# GMSL_SERIALIZER.net
KiCad netlist of a schematic drawn in Altium Designer
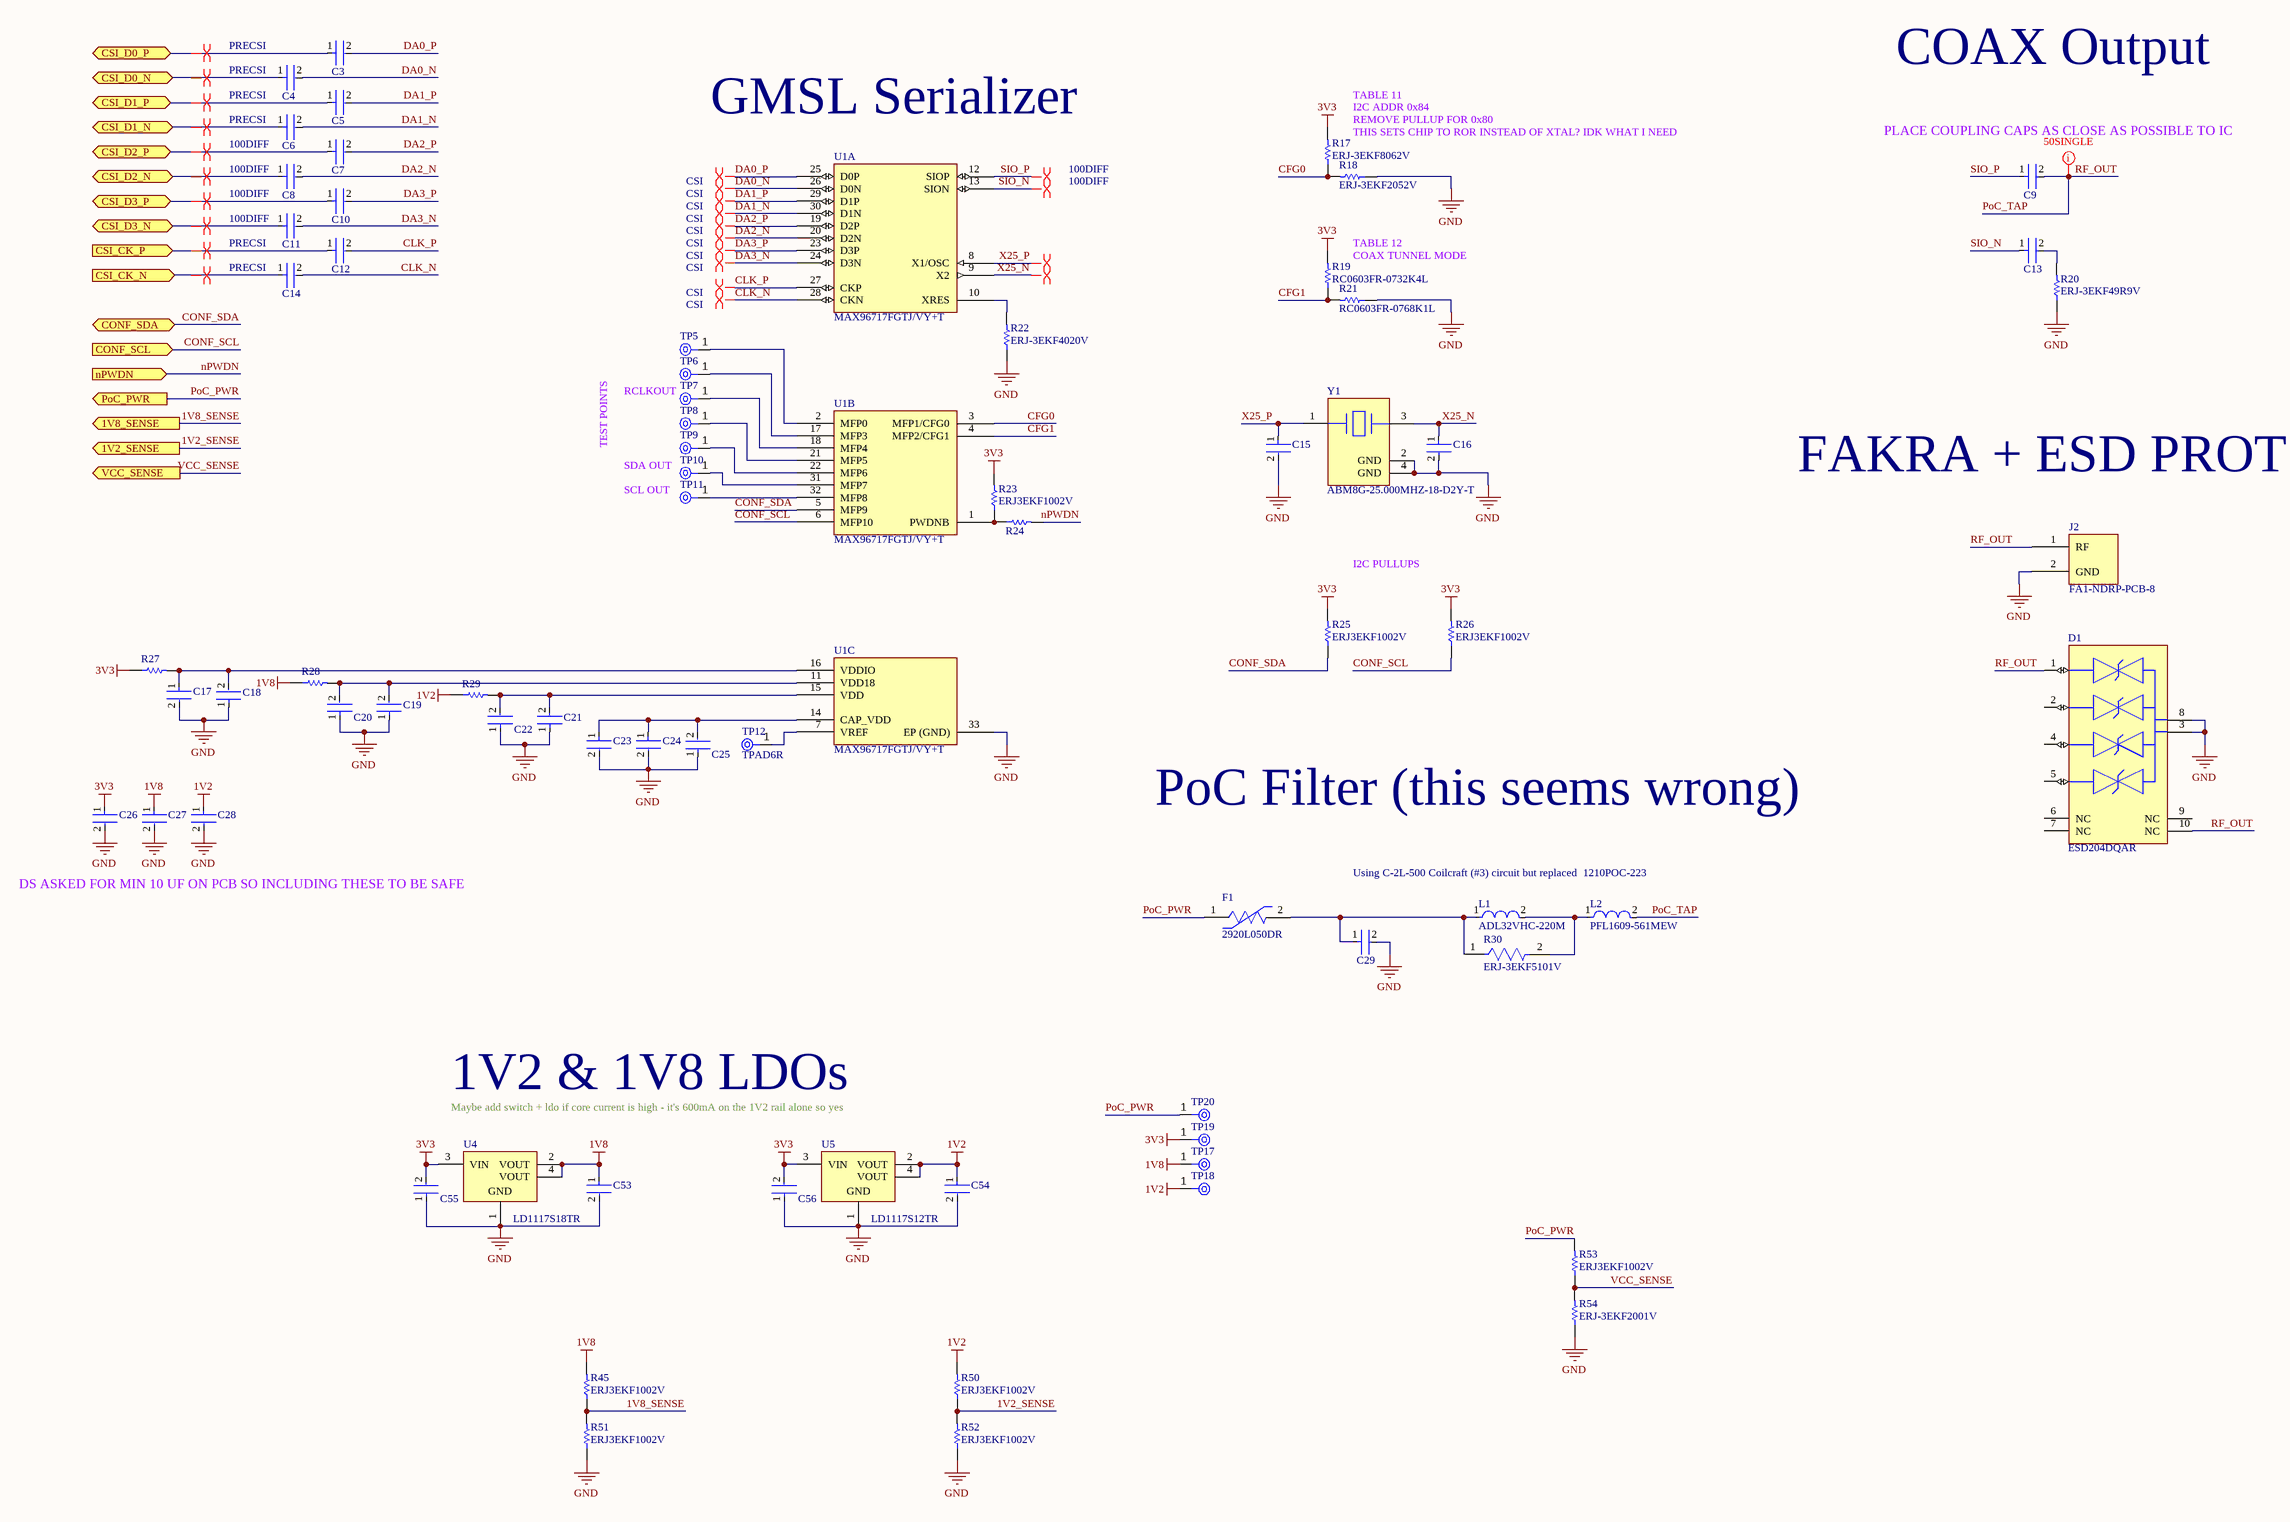
[diagram p0: GMSL_SERIALIZER.SchDoc]

(export (version "E")
  (design (tool "Eeschema 10.0.6"))
  (components
    (comp (ref "C3")
      (value "C1005X7R1H104K050BB")
      (footprint "FP-C1005-050-0_05-IPC_C")
      (description "Multilayer Ceramic Capacitors 100nF ±10% 50V X7R SMD 0402")
      (fields (field (name "VOLTAGE") "50V") (field (name "TOLERANCE") "10%"))
      (libsource (lib "Altium Content Vault") (part "b4654b650e69147ec39a6b967a45e02"))
    )
    (comp (ref "C4")
      (value "C1005X7R1H104K050BB")
      (footprint "FP-C1005-050-0_05-IPC_C")
      (description "Multilayer Ceramic Capacitors 100nF ±10% 50V X7R SMD 0402")
      (fields (field (name "VOLTAGE") "50V") (field (name "TOLERANCE") "10%"))
      (libsource (lib "Altium Content Vault") (part "b4654b650e69147ec39a6b967a45e02"))
    )
    (comp (ref "C5")
      (value "C1005X7R1H104K050BB")
      (footprint "FP-C1005-050-0_05-IPC_C")
      (description "Multilayer Ceramic Capacitors 100nF ±10% 50V X7R SMD 0402")
      (fields (field (name "VOLTAGE") "50V") (field (name "TOLERANCE") "10%"))
      (libsource (lib "Altium Content Vault") (part "b4654b650e69147ec39a6b967a45e02"))
    )
    (comp (ref "C6")
      (value "C1005X7R1H104K050BB")
      (footprint "FP-C1005-050-0_05-IPC_C")
      (description "Multilayer Ceramic Capacitors 100nF ±10% 50V X7R SMD 0402")
      (fields (field (name "VOLTAGE") "50V") (field (name "TOLERANCE") "10%"))
      (libsource (lib "Altium Content Vault") (part "b4654b650e69147ec39a6b967a45e02"))
    )
    (comp (ref "C7")
      (value "C1005X7R1H104K050BB")
      (footprint "FP-C1005-050-0_05-IPC_C")
      (description "Multilayer Ceramic Capacitors 100nF ±10% 50V X7R SMD 0402")
      (fields (field (name "VOLTAGE") "50V") (field (name "TOLERANCE") "10%"))
      (libsource (lib "Altium Content Vault") (part "b4654b650e69147ec39a6b967a45e02"))
    )
    (comp (ref "C8")
      (value "C1005X7R1H104K050BB")
      (footprint "FP-C1005-050-0_05-IPC_C")
      (description "Multilayer Ceramic Capacitors 100nF ±10% 50V X7R SMD 0402")
      (fields (field (name "VOLTAGE") "50V") (field (name "TOLERANCE") "10%"))
      (libsource (lib "Altium Content Vault") (part "b4654b650e69147ec39a6b967a45e02"))
    )
    (comp (ref "C9")
      (value "C1005X7R1H104K050BB")
      (footprint "FP-C1005-050-0_05-IPC_C")
      (description "Multilayer Ceramic Capacitors 100nF ±10% 50V X7R SMD 0402")
      (fields (field (name "VOLTAGE") "50V") (field (name "TOLERANCE") "10%"))
      (libsource (lib "Altium Content Vault") (part "b4654b650e69147ec39a6b967a45e02"))
    )
    (comp (ref "C10")
      (value "C1005X7R1H104K050BB")
      (footprint "FP-C1005-050-0_05-IPC_C")
      (description "Multilayer Ceramic Capacitors 100nF ±10% 50V X7R SMD 0402")
      (fields (field (name "VOLTAGE") "50V") (field (name "TOLERANCE") "10%"))
      (libsource (lib "Altium Content Vault") (part "b4654b650e69147ec39a6b967a45e02"))
    )
    (comp (ref "C11")
      (value "C1005X7R1H104K050BB")
      (footprint "FP-C1005-050-0_05-IPC_C")
      (description "Multilayer Ceramic Capacitors 100nF ±10% 50V X7R SMD 0402")
      (fields (field (name "VOLTAGE") "50V") (field (name "TOLERANCE") "10%"))
      (libsource (lib "Altium Content Vault") (part "b4654b650e69147ec39a6b967a45e02"))
    )
    (comp (ref "C12")
      (value "C1005X7R1H104K050BB")
      (footprint "FP-C1005-050-0_05-IPC_C")
      (description "Multilayer Ceramic Capacitors 100nF ±10% 50V X7R SMD 0402")
      (fields (field (name "VOLTAGE") "50V") (field (name "TOLERANCE") "10%"))
      (libsource (lib "Altium Content Vault") (part "b4654b650e69147ec39a6b967a45e02"))
    )
    (comp (ref "C13")
      (value "C1005X7R1H104K050BB")
      (footprint "FP-C1005-050-0_05-IPC_C")
      (description "Multilayer Ceramic Capacitors 100nF ±10% 50V X7R SMD 0402")
      (fields (field (name "VOLTAGE") "50V") (field (name "TOLERANCE") "10%"))
      (libsource (lib "Altium Content Vault") (part "b4654b650e69147ec39a6b967a45e02"))
    )
    (comp (ref "C14")
      (value "C1005X7R1H104K050BB")
      (footprint "FP-C1005-050-0_05-IPC_C")
      (description "Multilayer Ceramic Capacitors 100nF ±10% 50V X7R SMD 0402")
      (fields (field (name "VOLTAGE") "50V") (field (name "TOLERANCE") "10%"))
      (libsource (lib "Altium Content Vault") (part "b4654b650e69147ec39a6b967a45e02"))
    )
    (comp (ref "C15")
      (value "C0603C300J5GACTU")
      (footprint "FP-C0603C-CF-MFG")
      (description "CAP CER 30PF 50V 5% NP0 0603")
      (fields
        (field (name "MANUFACTURER") "KEMET")
        (field (name "OCTOPART") "https://octopart.com/c0603c300j5gactu-kemet-199455")
      )
      (libsource (lib "Altium Content Vault") (part "b4654b650e69147ec39a6b967a45e02"))
    )
    (comp (ref "C16")
      (value "C0603C300J5GACTU")
      (footprint "FP-C0603C-CF-MFG")
      (description "CAP CER 30PF 50V 5% NP0 0603")
      (fields
        (field (name "MANUFACTURER") "KEMET")
        (field (name "OCTOPART") "https://octopart.com/c0603c300j5gactu-kemet-199455")
      )
      (libsource (lib "Altium Content Vault") (part "b4654b650e69147ec39a6b967a45e02"))
    )
    (comp (ref "C17")
      (value "CL05A106MP5NUNC")
      (footprint "FP-CL05A106MP5NUNC-MFG")
      (description "CAP CER 10UF 10V X5R 0402")
      (fields
        (field (name "OCTOPART") "https://octopart.com/cl05a106mp5nunc-samsung-22457395")
        (field (name "TOLERANCE") "20%")
      )
      (libsource (lib "Altium Content Vault") (part "b4654b650e69147ec39a6b967a45e02"))
    )
    (comp (ref "C18")
      (value "C0402C103M5RACTU")
      (footprint "FP-C0402-BB-MFG")
      (description "CAP CER 10000PF 50V 20% X7R 0402")
      (fields
        (field (name "TOLERANCE") "0.2")
        (field (name "OCTOPART") "https://octopart.com/c0402c103m5ractu-kemet-17125571")
      )
      (libsource (lib "Altium Content Vault") (part "b4654b650e69147ec39a6b967a45e02"))
    )
    (comp (ref "C19")
      (value "C0402C103M5RACTU")
      (footprint "FP-C0402-BB-MFG")
      (description "CAP CER 10000PF 50V 20% X7R 0402")
      (fields
        (field (name "TOLERANCE") "0.2")
        (field (name "OCTOPART") "https://octopart.com/c0402c103m5ractu-kemet-17125571")
      )
      (libsource (lib "Altium Content Vault") (part "b4654b650e69147ec39a6b967a45e02"))
    )
    (comp (ref "C20")
      (value "C1005X7R1H104K050BB")
      (footprint "FP-C1005-050-0_05-IPC_C")
      (description "Multilayer Ceramic Capacitors 100nF ±10% 50V X7R SMD 0402")
      (fields (field (name "VOLTAGE") "50V") (field (name "TOLERANCE") "10%"))
      (libsource (lib "Altium Content Vault") (part "b4654b650e69147ec39a6b967a45e02"))
    )
    (comp (ref "C21")
      (value "C0402C103M5RACTU")
      (footprint "FP-C0402-BB-MFG")
      (description "CAP CER 10000PF 50V 20% X7R 0402")
      (fields
        (field (name "TOLERANCE") "0.2")
        (field (name "OCTOPART") "https://octopart.com/c0402c103m5ractu-kemet-17125571")
      )
      (libsource (lib "Altium Content Vault") (part "b4654b650e69147ec39a6b967a45e02"))
    )
    (comp (ref "C22")
      (value "C1005X7R1H104K050BB")
      (footprint "FP-C1005-050-0_05-IPC_C")
      (description "Multilayer Ceramic Capacitors 100nF ±10% 50V X7R SMD 0402")
      (fields (field (name "VOLTAGE") "50V") (field (name "TOLERANCE") "10%"))
      (libsource (lib "Altium Content Vault") (part "b4654b650e69147ec39a6b967a45e02"))
    )
    (comp (ref "C23")
      (value "CL05A106MP5NUNC")
      (footprint "FP-CL05A106MP5NUNC-MFG")
      (description "CAP CER 10UF 10V X5R 0402")
      (fields
        (field (name "OCTOPART") "https://octopart.com/cl05a106mp5nunc-samsung-22457395")
        (field (name "TOLERANCE") "20%")
      )
      (libsource (lib "Altium Content Vault") (part "b4654b650e69147ec39a6b967a45e02"))
    )
    (comp (ref "C24")
      (value "CL05A106MP5NUNC")
      (footprint "FP-CL05A106MP5NUNC-MFG")
      (description "CAP CER 10UF 10V X5R 0402")
      (fields
        (field (name "OCTOPART") "https://octopart.com/cl05a106mp5nunc-samsung-22457395")
        (field (name "TOLERANCE") "20%")
      )
      (libsource (lib "Altium Content Vault") (part "b4654b650e69147ec39a6b967a45e02"))
    )
    (comp (ref "C25")
      (value "C1005X7R1H104K050BB")
      (footprint "FP-C1005-050-0_05-IPC_C")
      (description "Multilayer Ceramic Capacitors 100nF ±10% 50V X7R SMD 0402")
      (fields (field (name "VOLTAGE") "50V") (field (name "TOLERANCE") "10%"))
      (libsource (lib "Altium Content Vault") (part "b4654b650e69147ec39a6b967a45e02"))
    )
    (comp (ref "C26")
      (value "CL05A106MP5NUNC")
      (footprint "FP-CL05A106MP5NUNC-MFG")
      (description "CAP CER 10UF 10V X5R 0402")
      (fields
        (field (name "OCTOPART") "https://octopart.com/cl05a106mp5nunc-samsung-22457395")
        (field (name "TOLERANCE") "20%")
      )
      (libsource (lib "Altium Content Vault") (part "b4654b650e69147ec39a6b967a45e02"))
    )
    (comp (ref "C27")
      (value "CL05A106MP5NUNC")
      (footprint "FP-CL05A106MP5NUNC-MFG")
      (description "CAP CER 10UF 10V X5R 0402")
      (fields
        (field (name "OCTOPART") "https://octopart.com/cl05a106mp5nunc-samsung-22457395")
        (field (name "TOLERANCE") "20%")
      )
      (libsource (lib "Altium Content Vault") (part "b4654b650e69147ec39a6b967a45e02"))
    )
    (comp (ref "C28")
      (value "CL05A106MP5NUNC")
      (footprint "FP-CL05A106MP5NUNC-MFG")
      (description "CAP CER 10UF 10V X5R 0402")
      (fields
        (field (name "OCTOPART") "https://octopart.com/cl05a106mp5nunc-samsung-22457395")
        (field (name "TOLERANCE") "20%")
      )
      (libsource (lib "Altium Content Vault") (part "b4654b650e69147ec39a6b967a45e02"))
    )
    (comp (ref "C29")
      (value "GRM21BR61E226ME44L")
      (footprint "FP-GRM21B-0_2-e0_2_0_7-IPC_B")
      (description "Chip Multilayer Ceramic Capacitors for General Purpose, 0805, 22uF, X5R, 15%, 20%, 25V")
      (fields (field (name "TOLERANCE") "20%") (field (name "VOLTAGE") "25V"))
      (libsource (lib "Altium Content Vault") (part "b4654b650e69147ec39a6b967a45e02"))
    )
    (comp (ref "C53")
      (value "GRM188R60J106ME47D")
      (footprint "FP-GRM188-0_1-e0_2_0_55-IPC_A")
      (description "Chip Multilayer Ceramic Capacitors for General Purpose, 0603, 10uF, X5R, 15%, 20%, 6.3V")
      (fields (field (name "VOLTAGE") "6.3V") (field (name "TOLERANCE") "20%"))
      (libsource (lib "Altium Content Vault") (part "02cd4be3c70576c341d710602a673aa"))
    )
    (comp (ref "C54")
      (value "GRM188R60J106ME47D")
      (footprint "FP-GRM188-0_1-e0_2_0_55-IPC_A")
      (description "Chip Multilayer Ceramic Capacitors for General Purpose, 0603, 10uF, X5R, 15%, 20%, 6.3V")
      (fields (field (name "VOLTAGE") "6.3V") (field (name "TOLERANCE") "20%"))
      (libsource (lib "Altium Content Vault") (part "02cd4be3c70576c341d710602a673aa"))
    )
    (comp (ref "C55")
      (value "C1005X7R1H104K050BB")
      (footprint "FP-C1005-050-0_05-IPC_C")
      (description "Multilayer Ceramic Capacitors 100nF ±10% 50V X7R SMD 0402")
      (fields (field (name "VOLTAGE") "50V") (field (name "TOLERANCE") "10%"))
      (libsource (lib "Altium Content Vault") (part "b4654b650e69147ec39a6b967a45e02"))
    )
    (comp (ref "C56")
      (value "C1005X7R1H104K050BB")
      (footprint "FP-C1005-050-0_05-IPC_C")
      (description "Multilayer Ceramic Capacitors 100nF ±10% 50V X7R SMD 0402")
      (fields (field (name "VOLTAGE") "50V") (field (name "TOLERANCE") "10%"))
      (libsource (lib "Altium Content Vault") (part "b4654b650e69147ec39a6b967a45e02"))
    )
    (comp (ref "D1")
      (value "ESD204DQAR")
      (footprint "FP-DQA0010A-MFG")
      (description "4-CHANNEL LOW-CAPACITANCE SURGE")
      (fields
        (field (name "MANUFACTURER") "Texas Instruments")
        (field (name "OCTOPART") "https://octopart.com/esd204dqar-texas+instruments-89917476")
      )
      (libsource (lib "Altium Content Vault") (part "1465e58c1818c7767b55926832f0bf5"))
    )
    (comp (ref "F1")
      (value "2920L050DR")
      (footprint "FP-2920L050DR-MFG")
      (description "PTC RESET FUSE 60V 500MA 2920")
      (libsource (lib "Altium Content Vault") (part "1c6d77a0208143737455a0c7eb396be"))
    )
    (comp (ref "J2")
      (value "FA1-NDRP-PCB-8")
      (footprint "FA1-NDRP-PCB-8-Footprint-1")
      (description "RF F Connector, Male, Board Mount, Solder Terminal, Plug")
      (libsource (lib "Space Concordia") (part "FA1-NDRP-PCB-8"))
    )
    (comp (ref "L1")
      (value "ADL32VHC-220M")
      (footprint "FP-1210POC-MFG")
      (description "NOT COILCRAFT - ACTUAL P# --> ADL32VHC-220M\r\n - Power Injection Chokes for PoC")
      (fields
        (field (name "MANUFACTURER") "coilcraft")
        (field (name "OCTOPART") "https://octopart.com/1210poc-223mrc-coilcraft-103207315")
      )
      (libsource (lib "Altium Content Vault") (part "725321dda6339637d4d059423bc1c3c"))
    )
    (comp (ref "L2")
      (value "PFL1609-561MEW")
      (footprint "FP-PFL1609-MFG")
      (description "Fixed Inductors PFL1609 Low Profile 0.56 uH 20 % 1.4 A")
      (fields (field (name "MANUFACTURER") "coilcraft") (field (name "TOLERANCE") "20%"))
      (libsource (lib "Altium Content Vault") (part "725321dda6339637d4d059423bc1c3c"))
    )
    (comp (ref "R17")
      (value "ERJ-3EKF8062V")
      (footprint "RESC1608X55X30LL15T15")
      (fields (field (name "MANUFACTURER") "Panasonic"))
      (libsource (lib "Altium Content Vault") (part "RES"))
    )
    (comp (ref "R18")
      (value "ERJ-3EKF2052V")
      (footprint "RESC1608X55X30NL15T15")
      (fields (field (name "MANUFACTURER") "Panasonic"))
      (libsource (lib "Altium Content Vault") (part "RES"))
    )
    (comp (ref "R19")
      (value "RC0603FR-0732K4L")
      (footprint "RESC1608X55X25ML10T15")
      (fields (field (name "MANUFACTURER") "Yageo"))
      (libsource (lib "Altium Content Vault") (part "RES"))
    )
    (comp (ref "R20")
      (value "ERJ-3EKF49R9V")
      (footprint "RESC1608X55X30ML15T15")
      (fields (field (name "MANUFACTURER") "Panasonic"))
      (libsource (lib "Altium Content Vault") (part "RES"))
    )
    (comp (ref "R21")
      (value "RC0603FR-0768K1L")
      (footprint "RESC1608X55X25LL10T15")
      (fields (field (name "MANUFACTURER") "Yageo"))
      (libsource (lib "Altium Content Vault") (part "RES"))
    )
    (comp (ref "R22")
      (value "ERJ-3EKF4020V")
      (footprint "RESC1608X55X30LL15T15")
      (fields (field (name "MANUFACTURER") "Panasonic"))
      (libsource (lib "Altium Content Vault") (part "RES"))
    )
    (comp (ref "R23")
      (value "ERJ3EKF1002V")
      (footprint "RESC1609X55X30LL15T15")
      (description "Chip Resistor, 10 KOhm, +/- 1%, 0.1 W, -55 to 155 degC, 0603 (1608 Metric), RoHS, Tape and Reel")
      (fields (field (name "TOLERANCE") "1%") (field (name "MANUFACTURER") "Panasonic"))
      (libsource (lib "Altium Content Vault") (part "RES-2"))
    )
    (comp (ref "R24")
      (value "0402 JUMPER")
      (footprint "RESC1005X40X25ML05T05")
      (description "READ THE NAME")
      (libsource (lib "Space Concordia") (part "CMP-009-00206-2"))
    )
    (comp (ref "R25")
      (value "ERJ3EKF1002V")
      (footprint "RESC1609X55X30LL15T15")
      (description "Chip Resistor, 10 KOhm, +/- 1%, 0.1 W, -55 to 155 degC, 0603 (1608 Metric), RoHS, Tape and Reel")
      (fields (field (name "TOLERANCE") "1%") (field (name "MANUFACTURER") "Panasonic"))
      (libsource (lib "Altium Content Vault") (part "RES-2"))
    )
    (comp (ref "R26")
      (value "ERJ3EKF1002V")
      (footprint "RESC1609X55X30LL15T15")
      (description "Chip Resistor, 10 KOhm, +/- 1%, 0.1 W, -55 to 155 degC, 0603 (1608 Metric), RoHS, Tape and Reel")
      (fields (field (name "TOLERANCE") "1%") (field (name "MANUFACTURER") "Panasonic"))
      (libsource (lib "Altium Content Vault") (part "RES-2"))
    )
    (comp (ref "R27")
      (value "RC0402JR-070RL")
      (footprint "RESC1005X40X25NL05T10")
      (fields (field (name "MANUFACTURER") "Yageo / Phycomp"))
      (libsource (lib "Altium Content Vault") (part "RES"))
    )
    (comp (ref "R28")
      (value "RC0402JR-070RL")
      (footprint "RESC1005X40X25NL05T10")
      (fields (field (name "MANUFACTURER") "Yageo / Phycomp"))
      (libsource (lib "Altium Content Vault") (part "RES"))
    )
    (comp (ref "R29")
      (value "RC0402JR-070RL")
      (footprint "RESC1005X40X25NL05T10")
      (fields (field (name "MANUFACTURER") "Yageo / Phycomp"))
      (libsource (lib "Altium Content Vault") (part "RES"))
    )
    (comp (ref "R30")
      (value "ERJ-3EKF5101V")
      (footprint "FP-ERJ3EK-MFG")
      (description "RES SMD 5.1K OHM 1% 1/10W 0603")
      (fields (field (name "TOLERANCE") "1%"))
      (libsource (lib "Altium Content Vault") (part "1029c3af85768c4190bb7ad29bc67b5"))
    )
    (comp (ref "R45")
      (value "ERJ3EKF1002V")
      (footprint "RESC1609X55X30LL15T15")
      (description "Chip Resistor, 10 KOhm, +/- 1%, 0.1 W, -55 to 155 degC, 0603 (1608 Metric), RoHS, Tape and Reel")
      (fields (field (name "TOLERANCE") "1%") (field (name "MANUFACTURER") "Panasonic"))
      (libsource (lib "Altium Content Vault") (part "RES-2"))
    )
    (comp (ref "R50")
      (value "ERJ3EKF1002V")
      (footprint "RESC1609X55X30LL15T15")
      (description "Chip Resistor, 10 KOhm, +/- 1%, 0.1 W, -55 to 155 degC, 0603 (1608 Metric), RoHS, Tape and Reel")
      (fields (field (name "TOLERANCE") "1%") (field (name "MANUFACTURER") "Panasonic"))
      (libsource (lib "Altium Content Vault") (part "RES-2"))
    )
    (comp (ref "R51")
      (value "ERJ3EKF1002V")
      (footprint "RESC1609X55X30LL15T15")
      (description "Chip Resistor, 10 KOhm, +/- 1%, 0.1 W, -55 to 155 degC, 0603 (1608 Metric), RoHS, Tape and Reel")
      (fields (field (name "TOLERANCE") "1%") (field (name "MANUFACTURER") "Panasonic"))
      (libsource (lib "Altium Content Vault") (part "RES-2"))
    )
    (comp (ref "R52")
      (value "ERJ3EKF1002V")
      (footprint "RESC1609X55X30LL15T15")
      (description "Chip Resistor, 10 KOhm, +/- 1%, 0.1 W, -55 to 155 degC, 0603 (1608 Metric), RoHS, Tape and Reel")
      (fields (field (name "TOLERANCE") "1%") (field (name "MANUFACTURER") "Panasonic"))
      (libsource (lib "Altium Content Vault") (part "RES-2"))
    )
    (comp (ref "R53")
      (value "ERJ3EKF1002V")
      (footprint "RESC1609X55X30LL15T15")
      (description "Chip Resistor, 10 KOhm, +/- 1%, 0.1 W, -55 to 155 degC, 0603 (1608 Metric), RoHS, Tape and Reel")
      (fields (field (name "TOLERANCE") "1%") (field (name "MANUFACTURER") "Panasonic"))
      (libsource (lib "Altium Content Vault") (part "RES-2"))
    )
    (comp (ref "R54")
      (value "ERJ-3EKF2001V")
      (footprint "RESC1608X55X30ML15T15")
      (fields (field (name "MANUFACTURER") "Panasonic"))
      (libsource (lib "Altium Content Vault") (part "RES"))
    )
    (comp (ref "TP5")
      (value "TPAD6R")
      (footprint "New footprint 1")
      (description "Test Point .6mm")
      (libsource (lib "Space Concordia") (part "TP"))
    )
    (comp (ref "TP6")
      (value "TPAD6R")
      (footprint "New footprint 1")
      (description "Test Point .6mm")
      (libsource (lib "Space Concordia") (part "TP"))
    )
    (comp (ref "TP7")
      (value "TPAD6R")
      (footprint "New footprint 1")
      (description "Test Point .6mm")
      (libsource (lib "Space Concordia") (part "TP"))
    )
    (comp (ref "TP8")
      (value "TPAD6R")
      (footprint "New footprint 1")
      (description "Test Point .6mm")
      (libsource (lib "Space Concordia") (part "TP"))
    )
    (comp (ref "TP9")
      (value "TPAD6R")
      (footprint "New footprint 1")
      (description "Test Point .6mm")
      (libsource (lib "Space Concordia") (part "TP"))
    )
    (comp (ref "TP10")
      (value "TPAD6R")
      (footprint "New footprint 1")
      (description "Test Point .6mm")
      (libsource (lib "Space Concordia") (part "TP"))
    )
    (comp (ref "TP11")
      (value "TPAD6R")
      (footprint "New footprint 1")
      (description "Test Point .6mm")
      (libsource (lib "Space Concordia") (part "TP"))
    )
    (comp (ref "TP12")
      (value "TPAD6R")
      (footprint "New footprint 1")
      (description "Test Point .6mm")
      (libsource (lib "Space Concordia") (part "TP"))
    )
    (comp (ref "TP17")
      (value "TPAD6R")
      (footprint "New footprint 1")
      (description "Test Point .6mm")
      (libsource (lib "Space Concordia") (part "TP"))
    )
    (comp (ref "TP18")
      (value "TPAD6R")
      (footprint "New footprint 1")
      (description "Test Point .6mm")
      (libsource (lib "Space Concordia") (part "TP"))
    )
    (comp (ref "TP19")
      (value "TPAD6R")
      (footprint "New footprint 1")
      (description "Test Point .6mm")
      (libsource (lib "Space Concordia") (part "TP"))
    )
    (comp (ref "TP20")
      (value "TPAD6R")
      (footprint "New footprint 1")
      (description "Test Point .6mm")
      (libsource (lib "Space Concordia") (part "TP"))
    )
    (comp (ref "U1")
      (value "MAX96717FGTJ/VY+T")
      (footprint "QFN50P500X500X80_HS-33N")
      (description "3Gbps Serializer TQFN-32 Serializers / Deserializers ROHS")
      (libsource (lib "Space Concordia") (part "MAX96717FGTJ_VY+T"))
    )
    (comp (ref "U4")
      (value "LD1117S18TR")
      (footprint "SOT-223_M")
      (description "Fixed Low Drop Positive Voltage Regulator, 1.8V, 4-Pin SOT-223, Tape and Reel")
      (libsource (lib "Altium Content Vault") (part "PM-REG-LD1117-SOT4"))
    )
    (comp (ref "U5")
      (value "LD1117S12TR")
      (footprint "SOT-223_M")
      (description "Fixed Low Drop Positive Voltage Regulator, 1.2V, 4-Pin SOT-223, Tape and Reel")
      (libsource (lib "Altium Content Vault") (part "PM-REG-LD1117-SOT4"))
    )
    (comp (ref "Y1")
      (value "ABM8G-25.000MHZ-18-D2Y-T")
      (footprint "FP-ABM8G-MFG")
      (description "Crystal 25MHz ±20ppm (Tol) ±30ppm (Stability) 18pF FUND 60Ω 4-Pin SMD T/R")
      (fields (field (name "TOLERANCE") "20ppm"))
      (libsource (lib "Altium Content Vault") (part "48e526d86b7f2615d98721063c72f49"))
    )
  )
  (nets
    (net (code "1") (name "/1V2_SENSE") (class "Default")
      (node (ref "R50") (pin "1") (pinfunction "1_1") (pintype "passive"))
      (node (ref "R52") (pin "2") (pinfunction "2_2") (pintype "passive"))
    )
    (net (code "2") (name "/1V8_SENSE") (class "Default")
      (node (ref "R45") (pin "1") (pinfunction "1_1") (pintype "passive"))
      (node (ref "R51") (pin "2") (pinfunction "2_2") (pintype "passive"))
    )
    (net (code "3") (name "/CFG0") (class "Default")
      (node (ref "R17") (pin "1") (pinfunction "1_1") (pintype "passive"))
      (node (ref "R18") (pin "2") (pinfunction "2_2") (pintype "passive"))
      (node (ref "U1") (pin "3") (pinfunction "MFP1/CFG0_3") (pintype "passive"))
    )
    (net (code "4") (name "/CFG1") (class "Default")
      (node (ref "R19") (pin "1") (pinfunction "1_1") (pintype "passive"))
      (node (ref "R21") (pin "2") (pinfunction "2_2") (pintype "passive"))
      (node (ref "U1") (pin "4") (pinfunction "MFP2/CFG1_4") (pintype "passive"))
    )
    (net (code "5") (name "/CLK_N") (class "Default")
      (node (ref "C14") (pin "2") (pinfunction "2_2") (pintype "passive"))
      (node (ref "U1") (pin "28") (pinfunction "CKN_28") (pintype "bidirectional"))
    )
    (net (code "6") (name "/CLK_P") (class "Default")
      (node (ref "C12") (pin "2") (pinfunction "2_2") (pintype "passive"))
      (node (ref "U1") (pin "27") (pinfunction "CKP_27") (pintype "bidirectional"))
    )
    (net (code "7") (name "/CONF_SCL") (class "Default")
      (node (ref "R26") (pin "1") (pinfunction "1_1") (pintype "passive"))
      (node (ref "U1") (pin "6") (pinfunction "MFP10_6") (pintype "passive"))
    )
    (net (code "8") (name "/CONF_SDA") (class "Default")
      (node (ref "R25") (pin "1") (pinfunction "1_1") (pintype "passive"))
      (node (ref "U1") (pin "5") (pinfunction "MFP9_5") (pintype "passive"))
    )
    (net (code "9") (name "/CSI_CK_N") (class "Default")
      (node (ref "C14") (pin "1") (pinfunction "1_1") (pintype "passive"))
    )
    (net (code "10") (name "/CSI_CK_P") (class "Default")
      (node (ref "C12") (pin "1") (pinfunction "1_1") (pintype "passive"))
    )
    (net (code "11") (name "/CSI_D0_N") (class "Default")
      (node (ref "C4") (pin "1") (pinfunction "1_1") (pintype "passive"))
    )
    (net (code "12") (name "/CSI_D0_P") (class "Default")
      (node (ref "C3") (pin "1") (pinfunction "1_1") (pintype "passive"))
    )
    (net (code "13") (name "/CSI_D1_N") (class "Default")
      (node (ref "C6") (pin "1") (pinfunction "1_1") (pintype "passive"))
    )
    (net (code "14") (name "/CSI_D1_P") (class "Default")
      (node (ref "C5") (pin "1") (pinfunction "1_1") (pintype "passive"))
    )
    (net (code "15") (name "/CSI_D2_N") (class "Default")
      (node (ref "C8") (pin "1") (pinfunction "1_1") (pintype "passive"))
    )
    (net (code "16") (name "/CSI_D2_P") (class "Default")
      (node (ref "C7") (pin "1") (pinfunction "1_1") (pintype "passive"))
    )
    (net (code "17") (name "/CSI_D3_N") (class "Default")
      (node (ref "C11") (pin "1") (pinfunction "1_1") (pintype "passive"))
    )
    (net (code "18") (name "/CSI_D3_P") (class "Default")
      (node (ref "C10") (pin "1") (pinfunction "1_1") (pintype "passive"))
    )
    (net (code "19") (name "/DA0_N") (class "Default")
      (node (ref "C4") (pin "2") (pinfunction "2_2") (pintype "passive"))
      (node (ref "U1") (pin "26") (pinfunction "D0N_26") (pintype "bidirectional"))
    )
    (net (code "20") (name "/DA0_P") (class "Default")
      (node (ref "C3") (pin "2") (pinfunction "2_2") (pintype "passive"))
      (node (ref "U1") (pin "25") (pinfunction "D0P_25") (pintype "bidirectional"))
    )
    (net (code "21") (name "/DA1_N") (class "Default")
      (node (ref "C6") (pin "2") (pinfunction "2_2") (pintype "passive"))
      (node (ref "U1") (pin "30") (pinfunction "D1N_30") (pintype "bidirectional"))
    )
    (net (code "22") (name "/DA1_P") (class "Default")
      (node (ref "C5") (pin "2") (pinfunction "2_2") (pintype "passive"))
      (node (ref "U1") (pin "29") (pinfunction "D1P_29") (pintype "bidirectional"))
    )
    (net (code "23") (name "/DA2_N") (class "Default")
      (node (ref "C8") (pin "2") (pinfunction "2_2") (pintype "passive"))
      (node (ref "U1") (pin "20") (pinfunction "D2N_20") (pintype "bidirectional"))
    )
    (net (code "24") (name "/DA2_P") (class "Default")
      (node (ref "C7") (pin "2") (pinfunction "2_2") (pintype "passive"))
      (node (ref "U1") (pin "19") (pinfunction "D2P_19") (pintype "bidirectional"))
    )
    (net (code "25") (name "/DA3_N") (class "Default")
      (node (ref "C11") (pin "2") (pinfunction "2_2") (pintype "passive"))
      (node (ref "U1") (pin "24") (pinfunction "D3N_24") (pintype "bidirectional"))
    )
    (net (code "26") (name "/DA3_P") (class "Default")
      (node (ref "C10") (pin "2") (pinfunction "2_2") (pintype "passive"))
      (node (ref "U1") (pin "23") (pinfunction "D3P_23") (pintype "bidirectional"))
    )
    (net (code "27") (name "/PoC_PWR") (class "Default")
      (node (ref "F1") (pin "1") (pinfunction "1_1") (pintype "passive"))
      (node (ref "R53") (pin "2") (pinfunction "2_2") (pintype "passive"))
      (node (ref "TP20") (pin "1") (pinfunction "TP_1") (pintype "passive"))
    )
    (net (code "28") (name "/PoC_TAP") (class "Default")
      (node (ref "C9") (pin "2") (pinfunction "2_2") (pintype "passive"))
      (node (ref "D1") (pin "1") (pinfunction "IO1_1") (pintype "bidirectional"))
      (node (ref "D1") (pin "10") (pinfunction "NC_10") (pintype "passive"))
      (node (ref "J2") (pin "1") (pinfunction "RF_1") (pintype "passive"))
      (node (ref "L2") (pin "2") (pinfunction "2_2") (pintype "passive"))
    )
    (net (code "29") (name "/SIO_N") (class "Default")
      (node (ref "C13") (pin "1") (pinfunction "1_1") (pintype "passive"))
      (node (ref "U1") (pin "13") (pinfunction "SION_13") (pintype "bidirectional"))
    )
    (net (code "30") (name "/SIO_P") (class "Default")
      (node (ref "C9") (pin "1") (pinfunction "1_1") (pintype "passive"))
      (node (ref "U1") (pin "12") (pinfunction "SIOP_12") (pintype "bidirectional"))
    )
    (net (code "31") (name "/VCC_SENSE") (class "Default")
      (node (ref "R53") (pin "1") (pinfunction "1_1") (pintype "passive"))
      (node (ref "R54") (pin "2") (pinfunction "2_2") (pintype "passive"))
    )
    (net (code "32") (name "/X25_N") (class "Default")
      (node (ref "C16") (pin "1") (pinfunction "1_1") (pintype "passive"))
      (node (ref "U1") (pin "9") (pinfunction "X2_9") (pintype "output"))
      (node (ref "Y1") (pin "3") (pinfunction "3_3") (pintype "passive"))
    )
    (net (code "33") (name "/X25_P") (class "Default")
      (node (ref "C15") (pin "1") (pinfunction "1_1") (pintype "passive"))
      (node (ref "U1") (pin "8") (pinfunction "X1/OSC_8") (pintype "input"))
      (node (ref "Y1") (pin "1") (pinfunction "1_1") (pintype "passive"))
    )
    (net (code "34") (name "/nPWDN") (class "Default")
      (node (ref "R24") (pin "2") (pinfunction "2_2") (pintype "passive"))
    )
    (net (code "35") (name "1V2") (class "Default")
      (node (ref "C28") (pin "1") (pinfunction "1_1") (pintype "passive"))
      (node (ref "C54") (pin "1") (pinfunction "1_1") (pintype "passive"))
      (node (ref "R29") (pin "1") (pinfunction "1_1") (pintype "passive"))
      (node (ref "R50") (pin "2") (pinfunction "2_2") (pintype "passive"))
      (node (ref "TP18") (pin "1") (pinfunction "TP_1") (pintype "passive"))
      (node (ref "U5") (pin "2") (pinfunction "VOUT_2") (pintype "power_in"))
      (node (ref "U5") (pin "4") (pinfunction "VOUT_4") (pintype "power_in"))
    )
    (net (code "36") (name "1V8") (class "Default")
      (node (ref "C27") (pin "1") (pinfunction "1_1") (pintype "passive"))
      (node (ref "C53") (pin "1") (pinfunction "1_1") (pintype "passive"))
      (node (ref "R28") (pin "1") (pinfunction "1_1") (pintype "passive"))
      (node (ref "R45") (pin "2") (pinfunction "2_2") (pintype "passive"))
      (node (ref "TP17") (pin "1") (pinfunction "TP_1") (pintype "passive"))
      (node (ref "U4") (pin "2") (pinfunction "VOUT_2") (pintype "power_in"))
      (node (ref "U4") (pin "4") (pinfunction "VOUT_4") (pintype "power_in"))
    )
    (net (code "37") (name "3V3") (class "Default")
      (node (ref "C26") (pin "1") (pinfunction "1_1") (pintype "passive"))
      (node (ref "C55") (pin "2") (pinfunction "2_2") (pintype "passive"))
      (node (ref "C56") (pin "2") (pinfunction "2_2") (pintype "passive"))
      (node (ref "R17") (pin "2") (pinfunction "2_2") (pintype "passive"))
      (node (ref "R19") (pin "2") (pinfunction "2_2") (pintype "passive"))
      (node (ref "R23") (pin "2") (pinfunction "2_2") (pintype "passive"))
      (node (ref "R25") (pin "2") (pinfunction "2_2") (pintype "passive"))
      (node (ref "R26") (pin "2") (pinfunction "2_2") (pintype "passive"))
      (node (ref "R27") (pin "1") (pinfunction "1_1") (pintype "passive"))
      (node (ref "TP19") (pin "1") (pinfunction "TP_1") (pintype "passive"))
      (node (ref "U4") (pin "3") (pinfunction "VIN_3") (pintype "power_in"))
      (node (ref "U5") (pin "3") (pinfunction "VIN_3") (pintype "power_in"))
    )
    (net (code "38") (name "GND") (class "Default")
      (node (ref "C15") (pin "2") (pinfunction "2_2") (pintype "passive"))
      (node (ref "C16") (pin "2") (pinfunction "2_2") (pintype "passive"))
      (node (ref "C17") (pin "2") (pinfunction "2_2") (pintype "passive"))
      (node (ref "C18") (pin "1") (pinfunction "1_1") (pintype "passive"))
      (node (ref "C19") (pin "1") (pinfunction "1_1") (pintype "passive"))
      (node (ref "C20") (pin "1") (pinfunction "1_1") (pintype "passive"))
      (node (ref "C21") (pin "1") (pinfunction "1_1") (pintype "passive"))
      (node (ref "C22") (pin "1") (pinfunction "1_1") (pintype "passive"))
      (node (ref "C23") (pin "2") (pinfunction "2_2") (pintype "passive"))
      (node (ref "C24") (pin "2") (pinfunction "2_2") (pintype "passive"))
      (node (ref "C25") (pin "1") (pinfunction "1_1") (pintype "passive"))
      (node (ref "C26") (pin "2") (pinfunction "2_2") (pintype "passive"))
      (node (ref "C27") (pin "2") (pinfunction "2_2") (pintype "passive"))
      (node (ref "C28") (pin "2") (pinfunction "2_2") (pintype "passive"))
      (node (ref "C29") (pin "2") (pinfunction "2_2") (pintype "passive"))
      (node (ref "C53") (pin "2") (pinfunction "2_2") (pintype "passive"))
      (node (ref "C54") (pin "2") (pinfunction "2_2") (pintype "passive"))
      (node (ref "C55") (pin "1") (pinfunction "1_1") (pintype "passive"))
      (node (ref "C56") (pin "1") (pinfunction "1_1") (pintype "passive"))
      (node (ref "D1") (pin "3") (pinfunction "GND_3") (pintype "power_in"))
      (node (ref "D1") (pin "8") (pinfunction "GND_8") (pintype "power_in"))
      (node (ref "J2") (pin "2") (pinfunction "GND_2") (pintype "passive"))
      (node (ref "R18") (pin "1") (pinfunction "1_1") (pintype "passive"))
      (node (ref "R20") (pin "1") (pinfunction "1_1") (pintype "passive"))
      (node (ref "R21") (pin "1") (pinfunction "1_1") (pintype "passive"))
      (node (ref "R22") (pin "1") (pinfunction "1_1") (pintype "passive"))
      (node (ref "R51") (pin "1") (pinfunction "1_1") (pintype "passive"))
      (node (ref "R52") (pin "1") (pinfunction "1_1") (pintype "passive"))
      (node (ref "R54") (pin "1") (pinfunction "1_1") (pintype "passive"))
      (node (ref "U1") (pin "33") (pinfunction "EP_(GND)_33") (pintype "power_in"))
      (node (ref "U4") (pin "1") (pinfunction "GND_1") (pintype "power_in"))
      (node (ref "U5") (pin "1") (pinfunction "GND_1") (pintype "power_in"))
      (node (ref "Y1") (pin "2") (pinfunction "GND_2") (pintype "power_in"))
      (node (ref "Y1") (pin "4") (pinfunction "GND_4") (pintype "power_in"))
    )
    (net (code "39") (name "Net-(C13-Pad2)") (class "Default")
      (node (ref "C13") (pin "2") (pinfunction "2_2") (pintype "passive"))
      (node (ref "R20") (pin "2") (pinfunction "2_2") (pintype "passive"))
    )
    (net (code "40") (name "Net-(C29-Pad1)") (class "Default")
      (node (ref "C29") (pin "1") (pinfunction "1_1") (pintype "passive"))
      (node (ref "F1") (pin "2") (pinfunction "2_2") (pintype "passive"))
      (node (ref "L1") (pin "1") (pinfunction "1_1") (pintype "passive"))
      (node (ref "R30") (pin "1") (pinfunction "1_1") (pintype "passive"))
    )
    (net (code "41") (name "Net-(L1-Pad2)") (class "Default")
      (node (ref "L1") (pin "2") (pinfunction "2_2") (pintype "passive"))
      (node (ref "L2") (pin "1") (pinfunction "1_1") (pintype "passive"))
      (node (ref "R30") (pin "2") (pinfunction "2_2") (pintype "passive"))
    )
    (net (code "42") (name "Net-(TP5-TP)") (class "Default")
      (node (ref "TP5") (pin "1") (pinfunction "TP_1") (pintype "passive"))
      (node (ref "U1") (pin "2") (pinfunction "MFP0_2") (pintype "passive"))
    )
    (net (code "43") (name "Net-(TP6-TP)") (class "Default")
      (node (ref "TP6") (pin "1") (pinfunction "TP_1") (pintype "passive"))
      (node (ref "U1") (pin "17") (pinfunction "MFP3_17") (pintype "passive"))
    )
    (net (code "44") (name "Net-(TP7-TP)") (class "Default")
      (node (ref "TP7") (pin "1") (pinfunction "TP_1") (pintype "passive"))
      (node (ref "U1") (pin "18") (pinfunction "MFP4_18") (pintype "passive"))
    )
    (net (code "45") (name "Net-(TP8-TP)") (class "Default")
      (node (ref "TP8") (pin "1") (pinfunction "TP_1") (pintype "passive"))
      (node (ref "U1") (pin "21") (pinfunction "MFP5_21") (pintype "passive"))
    )
    (net (code "46") (name "Net-(TP9-TP)") (class "Default")
      (node (ref "TP9") (pin "1") (pinfunction "TP_1") (pintype "passive"))
      (node (ref "U1") (pin "22") (pinfunction "MFP6_22") (pintype "passive"))
    )
    (net (code "47") (name "Net-(TP10-TP)") (class "Default")
      (node (ref "TP10") (pin "1") (pinfunction "TP_1") (pintype "passive"))
      (node (ref "U1") (pin "31") (pinfunction "MFP7_31") (pintype "passive"))
    )
    (net (code "48") (name "Net-(TP11-TP)") (class "Default")
      (node (ref "TP11") (pin "1") (pinfunction "TP_1") (pintype "passive"))
      (node (ref "U1") (pin "32") (pinfunction "MFP8_32") (pintype "passive"))
    )
    (net (code "49") (name "Net-(TP12-TP)") (class "Default")
      (node (ref "TP12") (pin "1") (pinfunction "TP_1") (pintype "passive"))
      (node (ref "U1") (pin "7") (pinfunction "VREF_7") (pintype "power_in"))
    )
    (net (code "50") (name "Net-(U1A-XRES)") (class "Default")
      (node (ref "R22") (pin "2") (pinfunction "2_2") (pintype "passive"))
      (node (ref "U1") (pin "10") (pinfunction "XRES_10") (pintype "passive"))
    )
    (net (code "51") (name "Net-(U1B-PWDNB)") (class "Default")
      (node (ref "R23") (pin "1") (pinfunction "1_1") (pintype "passive"))
      (node (ref "R24") (pin "1") (pinfunction "1_1") (pintype "passive"))
      (node (ref "U1") (pin "1") (pinfunction "PWDNB_1") (pintype "passive"))
    )
    (net (code "52") (name "Net-(U1C-CAP_VDD)") (class "Default")
      (node (ref "C23") (pin "1") (pinfunction "1_1") (pintype "passive"))
      (node (ref "C24") (pin "1") (pinfunction "1_1") (pintype "passive"))
      (node (ref "C25") (pin "2") (pinfunction "2_2") (pintype "passive"))
      (node (ref "U1") (pin "14") (pinfunction "CAP_VDD_14") (pintype "power_in"))
    )
    (net (code "53") (name "Net-(U1C-VDD)") (class "Default")
      (node (ref "C21") (pin "2") (pinfunction "2_2") (pintype "passive"))
      (node (ref "C22") (pin "2") (pinfunction "2_2") (pintype "passive"))
      (node (ref "R29") (pin "2") (pinfunction "2_2") (pintype "passive"))
      (node (ref "U1") (pin "15") (pinfunction "VDD_15") (pintype "power_in"))
    )
    (net (code "54") (name "Net-(U1C-VDD18)") (class "Default")
      (node (ref "C19") (pin "2") (pinfunction "2_2") (pintype "passive"))
      (node (ref "C20") (pin "2") (pinfunction "2_2") (pintype "passive"))
      (node (ref "R28") (pin "2") (pinfunction "2_2") (pintype "passive"))
      (node (ref "U1") (pin "11") (pinfunction "VDD18_11") (pintype "power_in"))
    )
    (net (code "55") (name "Net-(U1C-VDDIO)") (class "Default")
      (node (ref "C17") (pin "1") (pinfunction "1_1") (pintype "passive"))
      (node (ref "C18") (pin "2") (pinfunction "2_2") (pintype "passive"))
      (node (ref "R27") (pin "2") (pinfunction "2_2") (pintype "passive"))
      (node (ref "U1") (pin "16") (pinfunction "VDDIO_16") (pintype "power_in"))
    )
    (net (code "56") (name "unconnected-(D1-IO2-Pad2)") (class "Default")
      (node (ref "D1") (pin "2") (pinfunction "IO2_2") (pintype "bidirectional"))
    )
    (net (code "57") (name "unconnected-(D1-IO3-Pad4)") (class "Default")
      (node (ref "D1") (pin "4") (pinfunction "IO3_4") (pintype "bidirectional"))
    )
    (net (code "58") (name "unconnected-(D1-IO4-Pad5)") (class "Default")
      (node (ref "D1") (pin "5") (pinfunction "IO4_5") (pintype "bidirectional"))
    )
    (net (code "59") (name "unconnected-(D1-NC-Pad6)") (class "Default")
      (node (ref "D1") (pin "6") (pinfunction "NC_6") (pintype "passive"))
    )
    (net (code "60") (name "unconnected-(D1-NC-Pad7)") (class "Default")
      (node (ref "D1") (pin "7") (pinfunction "NC_7") (pintype "passive"))
    )
    (net (code "61") (name "unconnected-(D1-NC-Pad9)") (class "Default")
      (node (ref "D1") (pin "9") (pinfunction "NC_9") (pintype "passive"))
    )
  )
)
